# neopixel_square.net
KiCad netlist of a schematic drawn in EAGLE
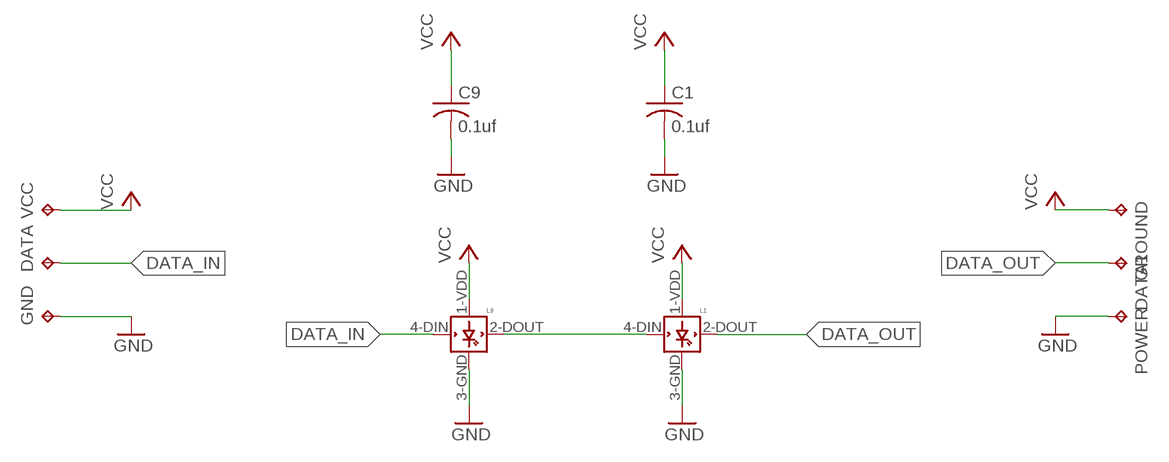
[diagram p0: schematic, sheet 1]

(export (version "E")
  (design (tool "Eeschema 10.0.6"))
  (components
    (comp (ref "C1")
      (value "0.1uf")
      (footprint "eagle-import:C0603")
      (libsource (lib "eagle-import") (part "C-USC0603"))
    )
    (comp (ref "C9")
      (value "0.1uf")
      (footprint "eagle-import:C0603")
      (libsource (lib "eagle-import") (part "C-USC0603"))
    )
    (comp (ref "DATA")
      (value "TPTP18R")
      (footprint "eagle-import:TP18R")
      (libsource (lib "eagle-import") (part "TPTP18R"))
    )
    (comp (ref "DATA1")
      (value "TPTP18R")
      (footprint "eagle-import:TP18R")
      (libsource (lib "eagle-import") (part "TPTP18R"))
    )
    (comp (ref "GND")
      (value "TPTP18SQ")
      (footprint "eagle-import:TP18SQ")
      (libsource (lib "eagle-import") (part "TPTP18SQ"))
    )
    (comp (ref "GROUND")
      (value "TPTP18R")
      (footprint "eagle-import:TP18R")
      (libsource (lib "eagle-import") (part "TPTP18R"))
    )
    (comp (ref "L1")
      (value "WS2812B")
      (footprint "eagle-import:WS2812B")
      (fields (field (name "SPICEPREFIX") "E"))
      (libsource (lib "eagle-import") (part "WS2812B"))
    )
    (comp (ref "L9")
      (value "WS2812B")
      (footprint "eagle-import:WS2812B")
      (fields (field (name "SPICEPREFIX") "E"))
      (libsource (lib "eagle-import") (part "WS2812B"))
    )
    (comp (ref "POWER")
      (value "TPTP18SQ")
      (footprint "eagle-import:TP18SQ")
      (libsource (lib "eagle-import") (part "TPTP18SQ"))
    )
    (comp (ref "VCC")
      (value "TPTP18R")
      (footprint "eagle-import:TP18R")
      (libsource (lib "eagle-import") (part "TPTP18R"))
    )
  )
  (nets
    (net (code "1") (name "DATA_IN") (class "Default")
      (node (ref "DATA") (pin "TP") (pinfunction "TP_TP") (pintype "input"))
      (node (ref "L9") (pin "4-DIN") (pinfunction "DIN_4-DIN") (pintype "input"))
    )
    (net (code "2") (name "DATA_OUT") (class "Default")
      (node (ref "DATA1") (pin "TP") (pinfunction "TP_TP") (pintype "input"))
      (node (ref "L1") (pin "2-DOUT") (pinfunction "DOUT_2-DOUT") (pintype "output"))
    )
    (net (code "3") (name "GND") (class "Default")
      (node (ref "C1") (pin "2") (pinfunction "2_2") (pintype "passive"))
      (node (ref "C9") (pin "2") (pinfunction "2_2") (pintype "passive"))
      (node (ref "GND") (pin "TP") (pinfunction "TP_TP") (pintype "input"))
      (node (ref "L1") (pin "3-GND") (pinfunction "GND_3-GND") (pintype "bidirectional"))
      (node (ref "L9") (pin "3-GND") (pinfunction "GND_3-GND") (pintype "bidirectional"))
      (node (ref "POWER") (pin "TP") (pinfunction "TP_TP") (pintype "input"))
    )
    (net (code "4") (name "Net-(L1-DIN)") (class "Default")
      (node (ref "L1") (pin "4-DIN") (pinfunction "DIN_4-DIN") (pintype "input"))
      (node (ref "L9") (pin "2-DOUT") (pinfunction "DOUT_2-DOUT") (pintype "output"))
    )
    (net (code "5") (name "VCC") (class "Default")
      (node (ref "C1") (pin "1") (pinfunction "1_1") (pintype "passive"))
      (node (ref "C9") (pin "1") (pinfunction "1_1") (pintype "passive"))
      (node (ref "GROUND") (pin "TP") (pinfunction "TP_TP") (pintype "input"))
      (node (ref "L1") (pin "1-VDD") (pinfunction "VDD_1-VDD") (pintype "bidirectional"))
      (node (ref "L9") (pin "1-VDD") (pinfunction "VDD_1-VDD") (pintype "bidirectional"))
      (node (ref "VCC") (pin "TP") (pinfunction "TP_TP") (pintype "input"))
    )
  )
)
